# ETHERNET.net
KiCad netlist of a schematic drawn in Altium Designer
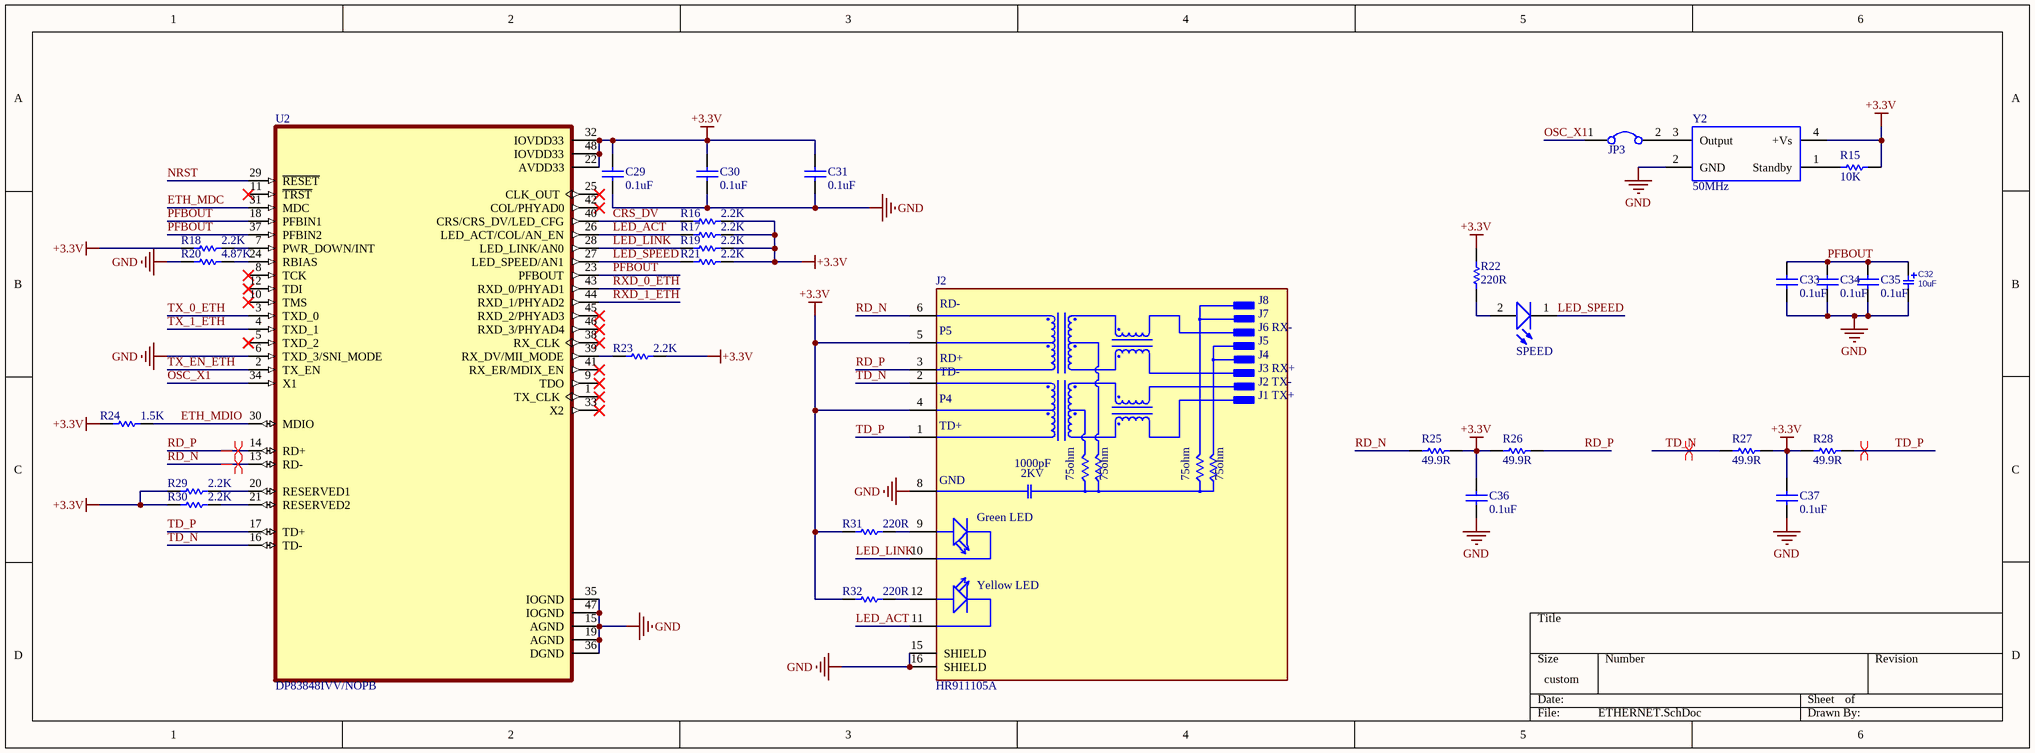
[diagram p0: ETHERNET.SchDoc]

(export (version "E")
  (design (tool "Eeschema 10.0.6"))
  (components
    (comp (ref "C29")
      (value "0.1uF")
      (footprint "CAPC3413X12N")
      (description "CAP 0805")
      (fields (field (name "DESIGNER") "Abbas Basereh"))
      (libsource (lib "Altium") (part "CAP SMD 0805"))
    )
    (comp (ref "C30")
      (value "0.1uF")
      (footprint "CAPC3413X12N")
      (description "CAP 0805")
      (fields (field (name "DESIGNER") "Abbas Basereh"))
      (libsource (lib "Altium") (part "CAP SMD 0805"))
    )
    (comp (ref "C31")
      (value "0.1uF")
      (footprint "CAPC3413X12N")
      (description "CAP 0805")
      (fields (field (name "DESIGNER") "Abbas Basereh"))
      (libsource (lib "Altium") (part "CAP SMD 0805"))
    )
    (comp (ref "C32")
      (value "10uF")
      (footprint "C_TN_6032")
      (description "CAP, SMD, TAN,")
      (libsource (lib "Passive") (part "CAP_SMD_TAN"))
    )
    (comp (ref "C33")
      (value "0.1uF")
      (footprint "CAPC3413X12N")
      (description "CAP 0805")
      (fields (field (name "DESIGNER") "Abbas Basereh"))
      (libsource (lib "Altium") (part "CAP SMD 0805"))
    )
    (comp (ref "C34")
      (value "0.1uF")
      (footprint "CAPC3413X12N")
      (description "CAP 0805")
      (fields (field (name "DESIGNER") "Abbas Basereh"))
      (libsource (lib "Altium") (part "CAP SMD 0805"))
    )
    (comp (ref "C35")
      (value "0.1uF")
      (footprint "CAPC3413X12N")
      (description "CAP 0805")
      (fields (field (name "DESIGNER") "Abbas Basereh"))
      (libsource (lib "Altium") (part "CAP SMD 0805"))
    )
    (comp (ref "C36")
      (value "0.1uF")
      (footprint "CAPC3413X12N")
      (description "CAP 0805")
      (fields (field (name "DESIGNER") "Abbas Basereh"))
      (libsource (lib "Altium") (part "CAP SMD 0805"))
    )
    (comp (ref "C37")
      (value "0.1uF")
      (footprint "CAPC3413X12N")
      (description "CAP 0805")
      (fields (field (name "DESIGNER") "Abbas Basereh"))
      (libsource (lib "Altium") (part "CAP SMD 0805"))
    )
    (comp (ref "J2")
      (value "HR911105A")
      (footprint "HANRUN_HR911105A")
      (description "DIP RJ45 Connector;")
      (fields (field (name "MF") "hanrun"))
      (libsource (lib "HR911105A") (part "HR911105A"))
    )
    (comp (ref "JP3")
      (value "Jumper")
      (footprint "Jumper Small - 2.54 - GRAY")
      (libsource (lib "Altium") (part "Jumper"))
    )
    (comp (ref "R15")
      (value "10K")
      (footprint "RESC3413X04N")
      (description "RES 0805")
      (fields (field (name "DESIGNER") "Abbas Basereh"))
      (libsource (lib "Altium") (part "RES 0805 0.125W"))
    )
    (comp (ref "R16")
      (value "2.2K")
      (footprint "RESC3413X04N")
      (description "RES 0805")
      (fields (field (name "DESIGNER") "Abbas Basereh"))
      (libsource (lib "Altium") (part "RES 0805 0.125W"))
    )
    (comp (ref "R17")
      (value "2.2K")
      (footprint "RESC3413X04N")
      (description "RES 0805")
      (fields (field (name "DESIGNER") "Abbas Basereh"))
      (libsource (lib "Altium") (part "RES 0805 0.125W"))
    )
    (comp (ref "R18")
      (value "2.2K")
      (footprint "RESC3413X04N")
      (description "RES 0805")
      (fields (field (name "DESIGNER") "Abbas Basereh"))
      (libsource (lib "Altium") (part "RES 0805 0.125W"))
    )
    (comp (ref "R19")
      (value "2.2K")
      (footprint "RESC3413X04N")
      (description "RES 0805")
      (fields (field (name "DESIGNER") "Abbas Basereh"))
      (libsource (lib "Altium") (part "RES 0805 0.125W"))
    )
    (comp (ref "R20")
      (value "4.87K")
      (footprint "RESC3413X04N")
      (description "RES 0805")
      (fields (field (name "DESIGNER") "Abbas Basereh"))
      (libsource (lib "Altium") (part "RES 0805 0.125W"))
    )
    (comp (ref "R21")
      (value "2.2K")
      (footprint "RESC3413X04N")
      (description "RES 0805")
      (fields (field (name "DESIGNER") "Abbas Basereh"))
      (libsource (lib "Altium") (part "RES 0805 0.125W"))
    )
    (comp (ref "R22")
      (value "220R")
      (footprint "RESC3413X04N")
      (description "RES 0805")
      (fields (field (name "DESIGNER") "Abbas Basereh"))
      (libsource (lib "Altium") (part "RES 0805 0.125W"))
    )
    (comp (ref "R23")
      (value "2.2K")
      (footprint "RESC3413X04N")
      (description "RES 0805")
      (fields (field (name "DESIGNER") "Abbas Basereh"))
      (libsource (lib "Altium") (part "RES 0805 0.125W"))
    )
    (comp (ref "R24")
      (value "1.5K")
      (footprint "RESC3413X04N")
      (description "RES 0805")
      (fields (field (name "DESIGNER") "Abbas Basereh"))
      (libsource (lib "Altium") (part "RES 0805 0.125W"))
    )
    (comp (ref "R25")
      (value "49.9R")
      (footprint "RESC3413X04N")
      (description "RES 0805")
      (fields (field (name "DESIGNER") "Abbas Basereh"))
      (libsource (lib "Altium") (part "RES 0805 0.125W"))
    )
    (comp (ref "R26")
      (value "49.9R")
      (footprint "RESC3413X04N")
      (description "RES 0805")
      (fields (field (name "DESIGNER") "Abbas Basereh"))
      (libsource (lib "Altium") (part "RES 0805 0.125W"))
    )
    (comp (ref "R27")
      (value "49.9R")
      (footprint "RESC3413X04N")
      (description "RES 0805")
      (fields (field (name "DESIGNER") "Abbas Basereh"))
      (libsource (lib "Altium") (part "RES 0805 0.125W"))
    )
    (comp (ref "R28")
      (value "49.9R")
      (footprint "RESC3413X04N")
      (description "RES 0805")
      (fields (field (name "DESIGNER") "Abbas Basereh"))
      (libsource (lib "Altium") (part "RES 0805 0.125W"))
    )
    (comp (ref "R29")
      (value "2.2K")
      (footprint "RESC3413X04N")
      (description "RES 0805")
      (fields (field (name "DESIGNER") "Abbas Basereh"))
      (libsource (lib "Altium") (part "RES 0805 0.125W"))
    )
    (comp (ref "R30")
      (value "2.2K")
      (footprint "RESC3413X04N")
      (description "RES 0805")
      (fields (field (name "DESIGNER") "Abbas Basereh"))
      (libsource (lib "Altium") (part "RES 0805 0.125W"))
    )
    (comp (ref "R31")
      (value "220R")
      (footprint "RESC3413X04N")
      (description "RES 0805")
      (fields (field (name "DESIGNER") "Abbas Basereh"))
      (libsource (lib "Altium") (part "RES 0805 0.125W"))
    )
    (comp (ref "R32")
      (value "220R")
      (footprint "RESC3413X04N")
      (description "RES 0805")
      (fields (field (name "DESIGNER") "Abbas Basereh"))
      (libsource (lib "Altium") (part "RES 0805 0.125W"))
    )
    (comp (ref "SPEED")
      (value "LED SMD PACKAGE")
      (footprint "LED_SMD_0805")
      (description "SMD Mono-color Chip LED Waterclear")
      (fields (field (name "PART NUMBER") "150080BS75000") (field (name "PUBLISHER") "Ali Hafizi"))
      (libsource (lib "Altium") (part "LED SMD PACKAGE"))
    )
    (comp (ref "U2")
      (value "DP83848IVV/NOPB")
      (footprint "LQFP-48")
      (fields (field (name "MF") "Texas Instruments"))
      (libsource (lib "DP83848IVV_NOPB") (part "DP83848IVV/NOPB"))
    )
    (comp (ref "Y2")
      (value "50MHz")
      (footprint "WE-SPXO_CFPS-72")
      (description "WE-SPXO Simple Packaged Quartz Oscillator, SMT, CFPS-72, 80MHz, 5V")
      (fields
        (field (name "MANUFACTURER") "Wurth Elektronik")
        (field (name "MANUFACTURER PART NUMBER") "831009443")
      )
      (libsource (lib "Crystal1") (part "831009443"))
    )
  )
  (nets
    (net (code "1") (name "+3.3V") (class "Default")
      (node (ref "C29") (pin "2") (pinfunction "2_2") (pintype "passive"))
      (node (ref "C30") (pin "2") (pinfunction "2_2") (pintype "passive"))
      (node (ref "C31") (pin "2") (pinfunction "2_2") (pintype "passive"))
      (node (ref "C36") (pin "2") (pinfunction "2_2") (pintype "passive"))
      (node (ref "C37") (pin "2") (pinfunction "2_2") (pintype "passive"))
      (node (ref "J2") (pin "4") (pinfunction "P4_4") (pintype "passive"))
      (node (ref "J2") (pin "5") (pinfunction "P5_5") (pintype "passive"))
      (node (ref "R15") (pin "2") (pinfunction "2_2") (pintype "passive"))
      (node (ref "R16") (pin "2") (pinfunction "2_2") (pintype "passive"))
      (node (ref "R17") (pin "2") (pinfunction "2_2") (pintype "passive"))
      (node (ref "R18") (pin "1") (pinfunction "1_1") (pintype "passive"))
      (node (ref "R19") (pin "2") (pinfunction "2_2") (pintype "passive"))
      (node (ref "R21") (pin "2") (pinfunction "2_2") (pintype "passive"))
      (node (ref "R22") (pin "2") (pinfunction "2_2") (pintype "passive"))
      (node (ref "R23") (pin "2") (pinfunction "2_2") (pintype "passive"))
      (node (ref "R24") (pin "1") (pinfunction "1_1") (pintype "passive"))
      (node (ref "R25") (pin "2") (pinfunction "2_2") (pintype "passive"))
      (node (ref "R26") (pin "1") (pinfunction "1_1") (pintype "passive"))
      (node (ref "R27") (pin "2") (pinfunction "2_2") (pintype "passive"))
      (node (ref "R28") (pin "1") (pinfunction "1_1") (pintype "passive"))
      (node (ref "R29") (pin "1") (pinfunction "1_1") (pintype "passive"))
      (node (ref "R30") (pin "1") (pinfunction "1_1") (pintype "passive"))
      (node (ref "R31") (pin "1") (pinfunction "1_1") (pintype "passive"))
      (node (ref "R32") (pin "1") (pinfunction "1_1") (pintype "passive"))
      (node (ref "U2") (pin "22") (pinfunction "AVDD33_22") (pintype "power_in"))
      (node (ref "U2") (pin "32") (pinfunction "IOVDD33_32") (pintype "power_in"))
      (node (ref "U2") (pin "48") (pinfunction "IOVDD33_48") (pintype "power_in"))
      (node (ref "Y2") (pin "4") (pinfunction "+Vs_4") (pintype "passive"))
    )
    (net (code "2") (name "/CRS_DV") (class "Default")
      (node (ref "R16") (pin "1") (pinfunction "1_1") (pintype "passive"))
      (node (ref "U2") (pin "40") (pinfunction "CRS/CRS_DV/LED_CFG_40") (pintype "output"))
    )
    (net (code "3") (name "/ETH_MDC") (class "Default")
      (node (ref "U2") (pin "31") (pinfunction "MDC_31") (pintype "input"))
    )
    (net (code "4") (name "/ETH_MDIO") (class "Default")
      (node (ref "R24") (pin "2") (pinfunction "2_2") (pintype "passive"))
      (node (ref "U2") (pin "30") (pinfunction "MDIO_30") (pintype "bidirectional"))
    )
    (net (code "5") (name "/LED_ACT") (class "Default")
      (node (ref "J2") (pin "11") (pinfunction "YC_11") (pintype "passive"))
      (node (ref "R17") (pin "1") (pinfunction "1_1") (pintype "passive"))
      (node (ref "U2") (pin "26") (pinfunction "LED_ACT/COL/AN_EN_26") (pintype "output"))
    )
    (net (code "6") (name "/LED_LINK") (class "Default")
      (node (ref "J2") (pin "10") (pinfunction "GC_10") (pintype "passive"))
      (node (ref "R19") (pin "1") (pinfunction "1_1") (pintype "passive"))
      (node (ref "U2") (pin "28") (pinfunction "LED_LINK/AN0_28") (pintype "output"))
    )
    (net (code "7") (name "/LED_SPEED") (class "Default")
      (node (ref "R21") (pin "1") (pinfunction "1_1") (pintype "passive"))
      (node (ref "SPEED") (pin "1") (pinfunction "K_1") (pintype "passive"))
      (node (ref "U2") (pin "27") (pinfunction "LED_SPEED/AN1_27") (pintype "output"))
    )
    (net (code "8") (name "/NRST") (class "Default")
      (node (ref "U2") (pin "29") (pinfunction "~{RESET}_29") (pintype "input"))
    )
    (net (code "9") (name "/OSC_X1") (class "Default")
      (node (ref "JP3") (pin "1") (pinfunction "1_1") (pintype "passive"))
      (node (ref "U2") (pin "34") (pinfunction "X1_34") (pintype "input"))
    )
    (net (code "10") (name "/PFBOUT") (class "Default")
      (node (ref "C32") (pin "1") (pinfunction "1_1") (pintype "passive"))
      (node (ref "C33") (pin "2") (pinfunction "2_2") (pintype "passive"))
      (node (ref "C34") (pin "2") (pinfunction "2_2") (pintype "passive"))
      (node (ref "C35") (pin "2") (pinfunction "2_2") (pintype "passive"))
      (node (ref "U2") (pin "18") (pinfunction "PFBIN1_18") (pintype "input"))
      (node (ref "U2") (pin "23") (pinfunction "PFBOUT_23") (pintype "output"))
      (node (ref "U2") (pin "37") (pinfunction "PFBIN2_37") (pintype "input"))
    )
    (net (code "11") (name "/RD_N") (class "Default")
      (node (ref "J2") (pin "6") (pinfunction "RD-_6") (pintype "passive"))
      (node (ref "R25") (pin "1") (pinfunction "1_1") (pintype "passive"))
      (node (ref "U2") (pin "13") (pinfunction "RD-_13") (pintype "bidirectional"))
    )
    (net (code "12") (name "/RD_P") (class "Default")
      (node (ref "J2") (pin "3") (pinfunction "RD+_3") (pintype "passive"))
      (node (ref "R26") (pin "2") (pinfunction "2_2") (pintype "passive"))
      (node (ref "U2") (pin "14") (pinfunction "RD+_14") (pintype "bidirectional"))
    )
    (net (code "13") (name "/RXD_0_ETH") (class "Default")
      (node (ref "U2") (pin "43") (pinfunction "RXD_0/PHYAD1_43") (pintype "output"))
    )
    (net (code "14") (name "/RXD_1_ETH") (class "Default")
      (node (ref "U2") (pin "44") (pinfunction "RXD_1/PHYAD2_44") (pintype "output"))
    )
    (net (code "15") (name "/TD_N") (class "Default")
      (node (ref "J2") (pin "2") (pinfunction "TD-_2") (pintype "passive"))
      (node (ref "R27") (pin "1") (pinfunction "1_1") (pintype "passive"))
      (node (ref "U2") (pin "16") (pinfunction "TD-_16") (pintype "bidirectional"))
    )
    (net (code "16") (name "/TD_P") (class "Default")
      (node (ref "J2") (pin "1") (pinfunction "TD+_1") (pintype "passive"))
      (node (ref "R28") (pin "2") (pinfunction "2_2") (pintype "passive"))
      (node (ref "U2") (pin "17") (pinfunction "TD+_17") (pintype "bidirectional"))
    )
    (net (code "17") (name "/TX_0_ETH") (class "Default")
      (node (ref "U2") (pin "3") (pinfunction "TXD_0_3") (pintype "input"))
    )
    (net (code "18") (name "/TX_1_ETH") (class "Default")
      (node (ref "U2") (pin "4") (pinfunction "TXD_1_4") (pintype "input"))
    )
    (net (code "19") (name "/TX_EN_ETH") (class "Default")
      (node (ref "U2") (pin "2") (pinfunction "TX_EN_2") (pintype "input"))
    )
    (net (code "20") (name "GND") (class "Default")
      (node (ref "C29") (pin "1") (pinfunction "1_1") (pintype "passive"))
      (node (ref "C30") (pin "1") (pinfunction "1_1") (pintype "passive"))
      (node (ref "C31") (pin "1") (pinfunction "1_1") (pintype "passive"))
      (node (ref "C32") (pin "2") (pinfunction "2_2") (pintype "passive"))
      (node (ref "C33") (pin "1") (pinfunction "1_1") (pintype "passive"))
      (node (ref "C34") (pin "1") (pinfunction "1_1") (pintype "passive"))
      (node (ref "C35") (pin "1") (pinfunction "1_1") (pintype "passive"))
      (node (ref "C36") (pin "1") (pinfunction "1_1") (pintype "passive"))
      (node (ref "C37") (pin "1") (pinfunction "1_1") (pintype "passive"))
      (node (ref "J2") (pin "15") (pinfunction "SHIELD_15") (pintype "passive"))
      (node (ref "J2") (pin "16") (pinfunction "SHIELD_16") (pintype "passive"))
      (node (ref "J2") (pin "8") (pinfunction "GND_8") (pintype "power_in"))
      (node (ref "R20") (pin "1") (pinfunction "1_1") (pintype "passive"))
      (node (ref "U2") (pin "15") (pinfunction "AGND_15") (pintype "power_in"))
      (node (ref "U2") (pin "19") (pinfunction "AGND_19") (pintype "power_in"))
      (node (ref "U2") (pin "35") (pinfunction "IOGND_35") (pintype "power_in"))
      (node (ref "U2") (pin "36") (pinfunction "DGND_36") (pintype "power_in"))
      (node (ref "U2") (pin "47") (pinfunction "IOGND_47") (pintype "power_in"))
      (node (ref "U2") (pin "6") (pinfunction "TXD_3/SNI_MODE_6") (pintype "input"))
      (node (ref "Y2") (pin "2") (pinfunction "GND_2") (pintype "passive"))
    )
    (net (code "21") (name "Net-(J2-GA)") (class "Default")
      (node (ref "J2") (pin "9") (pinfunction "GA_9") (pintype "passive"))
      (node (ref "R31") (pin "2") (pinfunction "2_2") (pintype "passive"))
    )
    (net (code "22") (name "Net-(J2-YA)") (class "Default")
      (node (ref "J2") (pin "12") (pinfunction "YA_12") (pintype "passive"))
      (node (ref "R32") (pin "2") (pinfunction "2_2") (pintype "passive"))
    )
    (net (code "23") (name "Net-(SPEED-A)") (class "Default")
      (node (ref "R22") (pin "1") (pinfunction "1_1") (pintype "passive"))
      (node (ref "SPEED") (pin "2") (pinfunction "A_2") (pintype "passive"))
    )
    (net (code "24") (name "Net-(U2-PWR_DOWN{slash}INT)") (class "Default")
      (node (ref "R18") (pin "2") (pinfunction "2_2") (pintype "passive"))
      (node (ref "U2") (pin "7") (pinfunction "PWR_DOWN/INT_7") (pintype "input"))
    )
    (net (code "25") (name "Net-(U2-RBIAS)") (class "Default")
      (node (ref "R20") (pin "2") (pinfunction "2_2") (pintype "passive"))
      (node (ref "U2") (pin "24") (pinfunction "RBIAS_24") (pintype "input"))
    )
    (net (code "26") (name "Net-(U2-RESERVED1)") (class "Default")
      (node (ref "R29") (pin "2") (pinfunction "2_2") (pintype "passive"))
      (node (ref "U2") (pin "20") (pinfunction "RESERVED1_20") (pintype "bidirectional"))
    )
    (net (code "27") (name "Net-(U2-RESERVED2)") (class "Default")
      (node (ref "R30") (pin "2") (pinfunction "2_2") (pintype "passive"))
      (node (ref "U2") (pin "21") (pinfunction "RESERVED2_21") (pintype "bidirectional"))
    )
    (net (code "28") (name "Net-(U2-RX_DV{slash}MII_MODE)") (class "Default")
      (node (ref "R23") (pin "1") (pinfunction "1_1") (pintype "passive"))
      (node (ref "U2") (pin "39") (pinfunction "RX_DV/MII_MODE_39") (pintype "output"))
    )
    (net (code "29") (name "Net-(Y2-Output)") (class "Default")
      (node (ref "JP3") (pin "2") (pinfunction "2_2") (pintype "passive"))
      (node (ref "Y2") (pin "3") (pinfunction "Output_3") (pintype "passive"))
    )
    (net (code "30") (name "Net-(Y2-Standby)") (class "Default")
      (node (ref "R15") (pin "1") (pinfunction "1_1") (pintype "passive"))
      (node (ref "Y2") (pin "1") (pinfunction "Standby_1") (pintype "passive"))
    )
    (net (code "31") (name "unconnected-(U2-CLK_OUT-Pad25)") (class "Default")
      (node (ref "U2") (pin "25") (pinfunction "CLK_OUT_25") (pintype "output+no_connect"))
    )
    (net (code "32") (name "unconnected-(U2-COL{slash}PHYAD0-Pad42)") (class "Default")
      (node (ref "U2") (pin "42") (pinfunction "COL/PHYAD0_42") (pintype "output+no_connect"))
    )
    (net (code "33") (name "unconnected-(U2-RXD_2{slash}PHYAD3-Pad45)") (class "Default")
      (node (ref "U2") (pin "45") (pinfunction "RXD_2/PHYAD3_45") (pintype "output+no_connect"))
    )
    (net (code "34") (name "unconnected-(U2-RXD_3{slash}PHYAD4-Pad46)") (class "Default")
      (node (ref "U2") (pin "46") (pinfunction "RXD_3/PHYAD4_46") (pintype "output+no_connect"))
    )
    (net (code "35") (name "unconnected-(U2-RX_CLK-Pad38)") (class "Default")
      (node (ref "U2") (pin "38") (pinfunction "RX_CLK_38") (pintype "output+no_connect"))
    )
    (net (code "36") (name "unconnected-(U2-RX_ER{slash}MDIX_EN-Pad41)") (class "Default")
      (node (ref "U2") (pin "41") (pinfunction "RX_ER/MDIX_EN_41") (pintype "output+no_connect"))
    )
    (net (code "37") (name "unconnected-(U2-TCK-Pad8)") (class "Default")
      (node (ref "U2") (pin "8") (pinfunction "TCK_8") (pintype "input+no_connect"))
    )
    (net (code "38") (name "unconnected-(U2-TDI-Pad12)") (class "Default")
      (node (ref "U2") (pin "12") (pinfunction "TDI_12") (pintype "input+no_connect"))
    )
    (net (code "39") (name "unconnected-(U2-TDO-Pad9)") (class "Default")
      (node (ref "U2") (pin "9") (pinfunction "TDO_9") (pintype "output+no_connect"))
    )
    (net (code "40") (name "unconnected-(U2-TMS-Pad10)") (class "Default")
      (node (ref "U2") (pin "10") (pinfunction "TMS_10") (pintype "input+no_connect"))
    )
    (net (code "41") (name "unconnected-(U2-TXD_2-Pad5)") (class "Default")
      (node (ref "U2") (pin "5") (pinfunction "TXD_2_5") (pintype "input+no_connect"))
    )
    (net (code "42") (name "unconnected-(U2-TX_CLK-Pad1)") (class "Default")
      (node (ref "U2") (pin "1") (pinfunction "TX_CLK_1") (pintype "output+no_connect"))
    )
    (net (code "43") (name "unconnected-(U2-X2-Pad33)") (class "Default")
      (node (ref "U2") (pin "33") (pinfunction "X2_33") (pintype "output+no_connect"))
    )
    (net (code "44") (name "unconnected-(U2-~{TRST}-Pad11)") (class "Default")
      (node (ref "U2") (pin "11") (pinfunction "~{TRST}_11") (pintype "input+no_connect"))
    )
  )
)
